# motorBoard.net
KiCad netlist of a schematic drawn in EAGLE
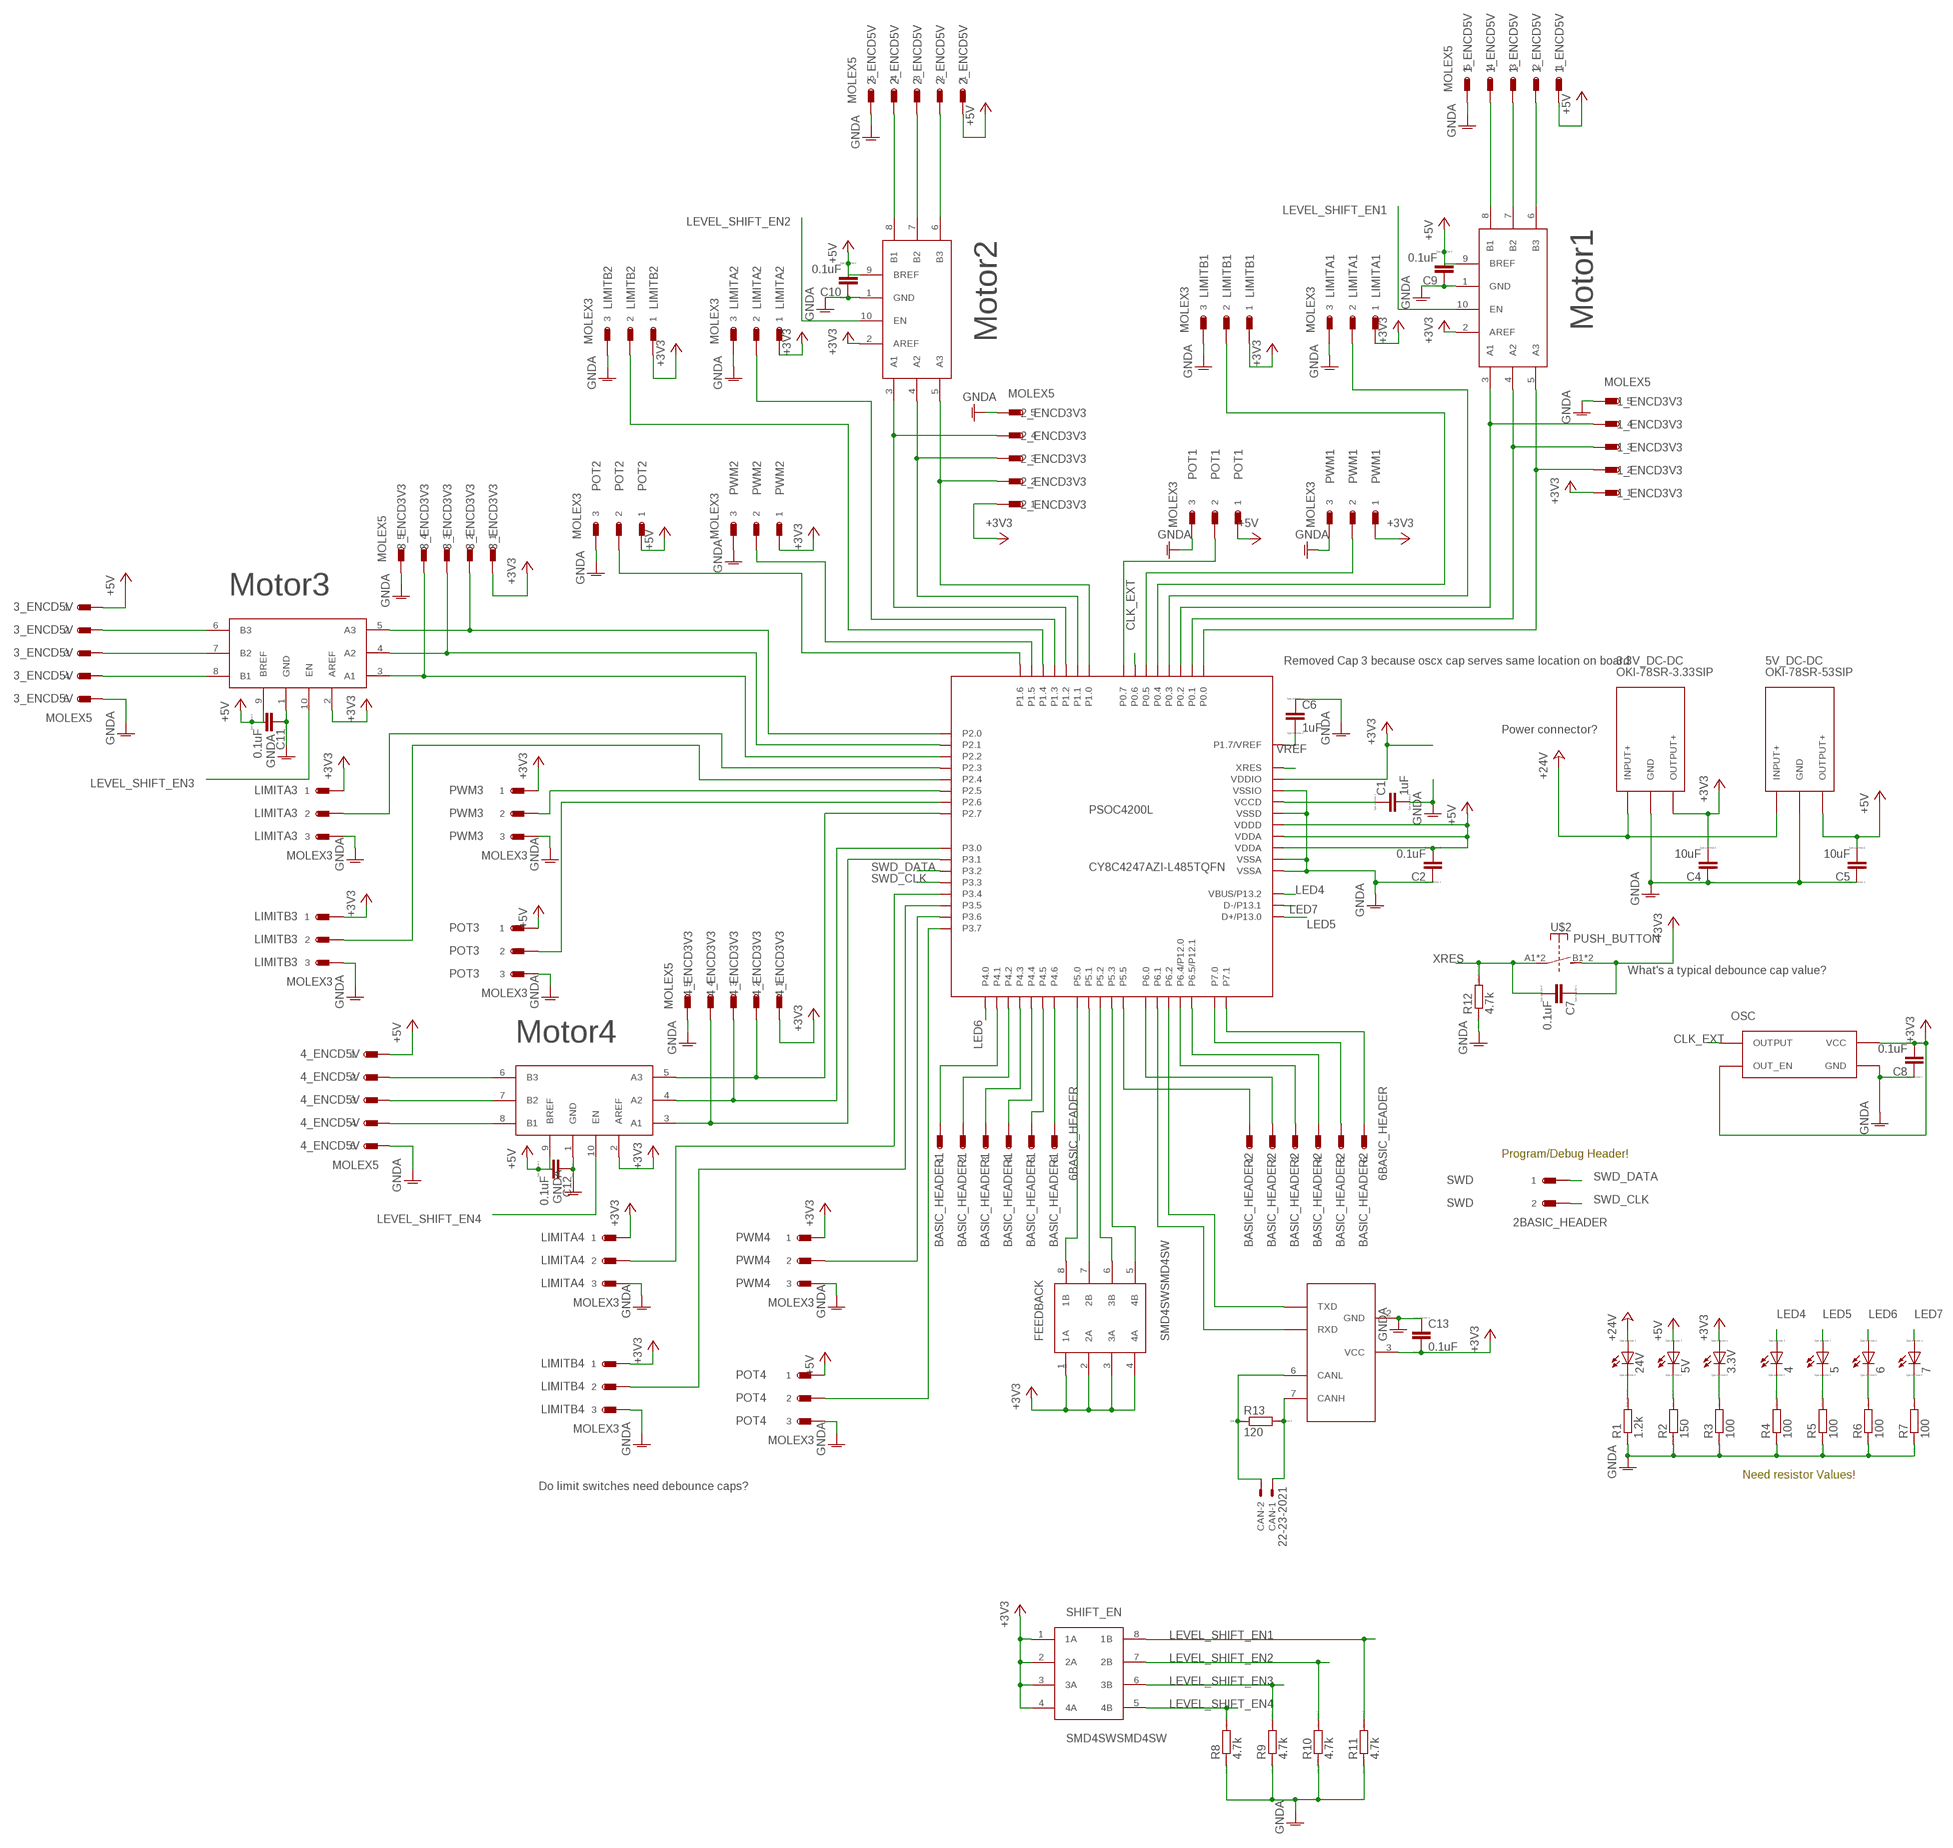
[diagram p0: schematic, sheet 1, part 1 of 2]
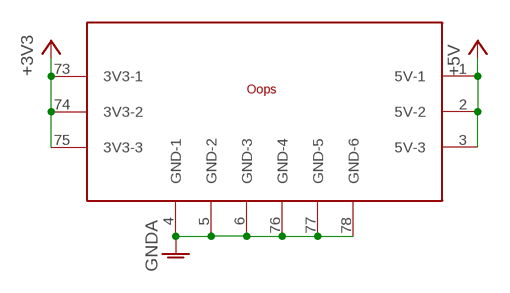
[diagram p1: schematic, sheet 1, part 2 of 2]

(export (version "E")
  (design (tool "Eeschema 10.0.6"))
  (components
    (comp (ref "1_ENCD3V3")
      (value "MOLEX5")
      (footprint "eagle-import:MOLEX22-23-2051")
      (libsource (lib "eagle-import") (part "MOLEX5"))
    )
    (comp (ref "1_ENCD5V")
      (value "MOLEX5")
      (footprint "eagle-import:MOLEX22-23-2051")
      (libsource (lib "eagle-import") (part "MOLEX5"))
    )
    (comp (ref "2_ENCD3V3")
      (value "MOLEX5")
      (footprint "eagle-import:MOLEX22-23-2051")
      (libsource (lib "eagle-import") (part "MOLEX5"))
    )
    (comp (ref "2_ENCD5V")
      (value "MOLEX5")
      (footprint "eagle-import:MOLEX22-23-2051")
      (libsource (lib "eagle-import") (part "MOLEX5"))
    )
    (comp (ref "3.3V")
      (value "LED_E")
      (footprint "eagle-import:LED_1206")
      (libsource (lib "eagle-import") (part "LED_E"))
    )
    (comp (ref "3.3V_DC-DC")
      (value "OKI-78SR-3.33SIP")
      (footprint "eagle-import:3SIP")
      (libsource (lib "eagle-import") (part "OKI-78SR-3.33SIP"))
    )
    (comp (ref "3_ENCD3V3")
      (value "MOLEX5")
      (footprint "eagle-import:MOLEX22-23-2051")
      (libsource (lib "eagle-import") (part "MOLEX5"))
    )
    (comp (ref "3_ENCD5V")
      (value "MOLEX5")
      (footprint "eagle-import:MOLEX22-23-2051")
      (libsource (lib "eagle-import") (part "MOLEX5"))
    )
    (comp (ref "4")
      (value "LED_E")
      (footprint "eagle-import:LED_1206")
      (libsource (lib "eagle-import") (part "LED_E"))
    )
    (comp (ref "4_ENCD3V3")
      (value "MOLEX5")
      (footprint "eagle-import:MOLEX22-23-2051")
      (libsource (lib "eagle-import") (part "MOLEX5"))
    )
    (comp (ref "4_ENCD5V")
      (value "MOLEX5")
      (footprint "eagle-import:MOLEX22-23-2051")
      (libsource (lib "eagle-import") (part "MOLEX5"))
    )
    (comp (ref "5")
      (value "LED_E")
      (footprint "eagle-import:LED_1206")
      (libsource (lib "eagle-import") (part "LED_E"))
    )
    (comp (ref "5V")
      (value "LED_E")
      (footprint "eagle-import:LED_1206")
      (libsource (lib "eagle-import") (part "LED_E"))
    )
    (comp (ref "5V_DC-DC")
      (value "OKI-78SR-53SIP")
      (footprint "eagle-import:3SIP")
      (libsource (lib "eagle-import") (part "OKI-78SR-53SIP"))
    )
    (comp (ref "6")
      (value "LED_E")
      (footprint "eagle-import:LED_1206")
      (libsource (lib "eagle-import") (part "LED_E"))
    )
    (comp (ref "7")
      (value "LED_E")
      (footprint "eagle-import:LED_1206")
      (libsource (lib "eagle-import") (part "LED_E"))
    )
    (comp (ref "24V")
      (value "LED_E")
      (footprint "eagle-import:LED_1206")
      (libsource (lib "eagle-import") (part "LED_E"))
    )
    (comp (ref "BASIC_HEADER1")
      (value "6BASIC_HEADER")
      (footprint "eagle-import:6SIP_HEADER")
      (libsource (lib "eagle-import") (part "6BASIC_HEADER"))
    )
    (comp (ref "BASIC_HEADER2")
      (value "6BASIC_HEADER")
      (footprint "eagle-import:6SIP_HEADER")
      (libsource (lib "eagle-import") (part "6BASIC_HEADER"))
    )
    (comp (ref "C1")
      (value "1uF")
      (footprint "eagle-import:C1206")
      (libsource (lib "eagle-import") (part "CC1206"))
    )
    (comp (ref "C2")
      (value "0.1uF")
      (footprint "eagle-import:C1206")
      (libsource (lib "eagle-import") (part "CC1206"))
    )
    (comp (ref "C4")
      (value "10uF")
      (footprint "eagle-import:C1206")
      (libsource (lib "eagle-import") (part "CC1206"))
    )
    (comp (ref "C5")
      (value "10uF")
      (footprint "eagle-import:C1206")
      (libsource (lib "eagle-import") (part "CC1206"))
    )
    (comp (ref "C6")
      (value "1uF")
      (footprint "eagle-import:C1206")
      (libsource (lib "eagle-import") (part "CC1206"))
    )
    (comp (ref "C7")
      (value "0.1uF")
      (footprint "eagle-import:C1206")
      (libsource (lib "eagle-import") (part "CC1206"))
    )
    (comp (ref "C8")
      (value "0.1uF")
      (footprint "eagle-import:C1206")
      (libsource (lib "eagle-import") (part "CC1206"))
    )
    (comp (ref "C9")
      (value "0.1uF")
      (footprint "eagle-import:C1206")
      (libsource (lib "eagle-import") (part "CC1206"))
    )
    (comp (ref "C10")
      (value "0.1uF")
      (footprint "eagle-import:C1206")
      (libsource (lib "eagle-import") (part "CC1206"))
    )
    (comp (ref "C11")
      (value "0.1uF")
      (footprint "eagle-import:C1206")
      (libsource (lib "eagle-import") (part "CC1206"))
    )
    (comp (ref "C12")
      (value "0.1uF")
      (footprint "eagle-import:C1206")
      (libsource (lib "eagle-import") (part "CC1206"))
    )
    (comp (ref "C13")
      (value "0.1uF")
      (footprint "eagle-import:C1206")
      (libsource (lib "eagle-import") (part "CC1206"))
    )
    (comp (ref "CAN")
      (value "22-23-2021")
      (footprint "eagle-import:22-23-2021")
      (fields (field (name "MF") "MOLEX"))
      (libsource (lib "eagle-import") (part "22-23-2021"))
    )
    (comp (ref "FEEDBACK")
      (value "SMD4SWSMD4SW")
      (footprint "eagle-import:GULL8")
      (libsource (lib "eagle-import") (part "SMD4SWSMD4SW"))
    )
    (comp (ref "LIMITA1")
      (value "MOLEX3")
      (footprint "eagle-import:MOLEX22-23-2031")
      (libsource (lib "eagle-import") (part "MOLEX3"))
    )
    (comp (ref "LIMITA2")
      (value "MOLEX3")
      (footprint "eagle-import:MOLEX22-23-2031")
      (libsource (lib "eagle-import") (part "MOLEX3"))
    )
    (comp (ref "LIMITA3")
      (value "MOLEX3")
      (footprint "eagle-import:MOLEX22-23-2031")
      (libsource (lib "eagle-import") (part "MOLEX3"))
    )
    (comp (ref "LIMITA4")
      (value "MOLEX3")
      (footprint "eagle-import:MOLEX22-23-2031")
      (libsource (lib "eagle-import") (part "MOLEX3"))
    )
    (comp (ref "LIMITB1")
      (value "MOLEX3")
      (footprint "eagle-import:MOLEX22-23-2031")
      (libsource (lib "eagle-import") (part "MOLEX3"))
    )
    (comp (ref "LIMITB2")
      (value "MOLEX3")
      (footprint "eagle-import:MOLEX22-23-2031")
      (libsource (lib "eagle-import") (part "MOLEX3"))
    )
    (comp (ref "LIMITB3")
      (value "MOLEX3")
      (footprint "eagle-import:MOLEX22-23-2031")
      (libsource (lib "eagle-import") (part "MOLEX3"))
    )
    (comp (ref "LIMITB4")
      (value "MOLEX3")
      (footprint "eagle-import:MOLEX22-23-2031")
      (libsource (lib "eagle-import") (part "MOLEX3"))
    )
    (comp (ref "OSC")
      (value "ESPSON_SG-646PCE_CRYSTAL_OSCILLATOREPSON_SG-646PCE_32MHZ")
      (footprint "eagle-import:4SOJ-5.08MM")
      (libsource (lib "eagle-import") (part "ESPSON_SG-646PCE_CRYSTAL_OSCILLATOREPSON_SG-646PCE_32MHZ"))
    )
    (comp (ref "POT1")
      (value "MOLEX3")
      (footprint "eagle-import:MOLEX22-23-2031")
      (libsource (lib "eagle-import") (part "MOLEX3"))
    )
    (comp (ref "POT2")
      (value "MOLEX3")
      (footprint "eagle-import:MOLEX22-23-2031")
      (libsource (lib "eagle-import") (part "MOLEX3"))
    )
    (comp (ref "POT3")
      (value "MOLEX3")
      (footprint "eagle-import:MOLEX22-23-2031")
      (libsource (lib "eagle-import") (part "MOLEX3"))
    )
    (comp (ref "POT4")
      (value "MOLEX3")
      (footprint "eagle-import:MOLEX22-23-2031")
      (libsource (lib "eagle-import") (part "MOLEX3"))
    )
    (comp (ref "PSOC4200L")
      (value "CY8C4247AZI-L485TQFN")
      (footprint "eagle-import:TQPF64-10MM")
      (libsource (lib "eagle-import") (part "CY8C4247AZI-L485TQFN"))
    )
    (comp (ref "PWM1")
      (value "MOLEX3")
      (footprint "eagle-import:MOLEX22-23-2031")
      (libsource (lib "eagle-import") (part "MOLEX3"))
    )
    (comp (ref "PWM2")
      (value "MOLEX3")
      (footprint "eagle-import:MOLEX22-23-2031")
      (libsource (lib "eagle-import") (part "MOLEX3"))
    )
    (comp (ref "PWM3")
      (value "MOLEX3")
      (footprint "eagle-import:MOLEX22-23-2031")
      (libsource (lib "eagle-import") (part "MOLEX3"))
    )
    (comp (ref "PWM4")
      (value "MOLEX3")
      (footprint "eagle-import:MOLEX22-23-2031")
      (libsource (lib "eagle-import") (part "MOLEX3"))
    )
    (comp (ref "R1")
      (value "1.2k")
      (footprint "eagle-import:R1206")
      (libsource (lib "eagle-import") (part "RR1206"))
    )
    (comp (ref "R2")
      (value "150")
      (footprint "eagle-import:R1206")
      (libsource (lib "eagle-import") (part "RR1206"))
    )
    (comp (ref "R3")
      (value "100")
      (footprint "eagle-import:R1206")
      (libsource (lib "eagle-import") (part "RR1206"))
    )
    (comp (ref "R4")
      (value "100")
      (footprint "eagle-import:R1206")
      (libsource (lib "eagle-import") (part "RR1206"))
    )
    (comp (ref "R5")
      (value "100")
      (footprint "eagle-import:R1206")
      (libsource (lib "eagle-import") (part "RR1206"))
    )
    (comp (ref "R6")
      (value "100")
      (footprint "eagle-import:R1206")
      (libsource (lib "eagle-import") (part "RR1206"))
    )
    (comp (ref "R7")
      (value "100")
      (footprint "eagle-import:R1206")
      (libsource (lib "eagle-import") (part "RR1206"))
    )
    (comp (ref "R8")
      (value "4.7k")
      (footprint "eagle-import:R1206")
      (libsource (lib "eagle-import") (part "RR1206"))
    )
    (comp (ref "R9")
      (value "4.7k")
      (footprint "eagle-import:R1206")
      (libsource (lib "eagle-import") (part "RR1206"))
    )
    (comp (ref "R10")
      (value "4.7k")
      (footprint "eagle-import:R1206")
      (libsource (lib "eagle-import") (part "RR1206"))
    )
    (comp (ref "R11")
      (value "4.7k")
      (footprint "eagle-import:R1206")
      (libsource (lib "eagle-import") (part "RR1206"))
    )
    (comp (ref "R12")
      (value "4.7k")
      (footprint "eagle-import:R1206")
      (libsource (lib "eagle-import") (part "RR1206"))
    )
    (comp (ref "R13")
      (value "120")
      (footprint "eagle-import:R1206")
      (libsource (lib "eagle-import") (part "RR1206"))
    )
    (comp (ref "SHIFT1")
      (value "LEVEL-SHIFTER_NVT2003DPNVT_2003DP_LEVEL_SHIFTER")
      (footprint "eagle-import:TSSOP10")
      (libsource (lib "eagle-import") (part "LEVEL-SHIFTER_NVT2003DPNVT_2003DP_LEVEL_SHIFTER"))
    )
    (comp (ref "SHIFT2")
      (value "LEVEL-SHIFTER_NVT2003DPNVT_2003DP_LEVEL_SHIFTER")
      (footprint "eagle-import:TSSOP10")
      (libsource (lib "eagle-import") (part "LEVEL-SHIFTER_NVT2003DPNVT_2003DP_LEVEL_SHIFTER"))
    )
    (comp (ref "SHIFT3")
      (value "LEVEL-SHIFTER_NVT2003DPNVT_2003DP_LEVEL_SHIFTER")
      (footprint "eagle-import:TSSOP10")
      (libsource (lib "eagle-import") (part "LEVEL-SHIFTER_NVT2003DPNVT_2003DP_LEVEL_SHIFTER"))
    )
    (comp (ref "SHIFT4")
      (value "LEVEL-SHIFTER_NVT2003DPNVT_2003DP_LEVEL_SHIFTER")
      (footprint "eagle-import:TSSOP10")
      (libsource (lib "eagle-import") (part "LEVEL-SHIFTER_NVT2003DPNVT_2003DP_LEVEL_SHIFTER"))
    )
    (comp (ref "SHIFT_EN")
      (value "SMD4SWSMD4SW")
      (footprint "eagle-import:GULL8")
      (libsource (lib "eagle-import") (part "SMD4SWSMD4SW"))
    )
    (comp (ref "SWD")
      (value "2BASIC_HEADER")
      (footprint "eagle-import:2SIP_HEADER")
      (libsource (lib "eagle-import") (part "2BASIC_HEADER"))
    )
    (comp (ref "TCAN")
      (value "TCAN332TCAN332")
      (footprint "eagle-import:8SOIC3.9")
      (libsource (lib "eagle-import") (part "TCAN332TCAN332"))
    )
    (comp (ref "U$1")
      (value "OOPS_SPACE")
      (footprint "eagle-import:OOPS_SPACE")
      (libsource (lib "eagle-import") (part "OOPS_SPACE"))
    )
    (comp (ref "U$2")
      (value "PUSH_BUTTON")
      (footprint "eagle-import:PUSH_BUTTON")
      (libsource (lib "eagle-import") (part "PUSH_BUTTON"))
    )
  )
  (nets
    (net (code "1") (name "+3V3") (class "Default")
      (node (ref "1_ENCD3V3") (pin "1") (pinfunction "1_1") (pintype "bidirectional"))
      (node (ref "2_ENCD3V3") (pin "1") (pinfunction "1_1") (pintype "bidirectional"))
      (node (ref "3.3V") (pin "A") (pinfunction "A_A") (pintype "passive"))
      (node (ref "3.3V_DC-DC") (pin "3") (pinfunction "OUTPUT+_3") (pintype "power_in"))
      (node (ref "3_ENCD3V3") (pin "1") (pinfunction "1_1") (pintype "bidirectional"))
      (node (ref "4_ENCD3V3") (pin "1") (pinfunction "1_1") (pintype "bidirectional"))
      (node (ref "C13") (pin "2") (pinfunction "2_2") (pintype "passive"))
      (node (ref "C4") (pin "2") (pinfunction "2_2") (pintype "passive"))
      (node (ref "C7") (pin "1") (pinfunction "1_1") (pintype "passive"))
      (node (ref "C8") (pin "2") (pinfunction "2_2") (pintype "passive"))
      (node (ref "FEEDBACK") (pin "1") (pinfunction "1A_1") (pintype "bidirectional"))
      (node (ref "FEEDBACK") (pin "2") (pinfunction "2A_2") (pintype "bidirectional"))
      (node (ref "FEEDBACK") (pin "3") (pinfunction "3A_3") (pintype "bidirectional"))
      (node (ref "FEEDBACK") (pin "4") (pinfunction "4A_4") (pintype "bidirectional"))
      (node (ref "LIMITA1") (pin "1") (pinfunction "1_1") (pintype "bidirectional"))
      (node (ref "LIMITA2") (pin "1") (pinfunction "1_1") (pintype "bidirectional"))
      (node (ref "LIMITA3") (pin "1") (pinfunction "1_1") (pintype "bidirectional"))
      (node (ref "LIMITA4") (pin "1") (pinfunction "1_1") (pintype "bidirectional"))
      (node (ref "LIMITB1") (pin "1") (pinfunction "1_1") (pintype "bidirectional"))
      (node (ref "LIMITB2") (pin "1") (pinfunction "1_1") (pintype "bidirectional"))
      (node (ref "LIMITB3") (pin "1") (pinfunction "1_1") (pintype "bidirectional"))
      (node (ref "LIMITB4") (pin "1") (pinfunction "1_1") (pintype "bidirectional"))
      (node (ref "OSC") (pin "1") (pinfunction "OUT_EN_1") (pintype "input"))
      (node (ref "OSC") (pin "4") (pinfunction "VCC_4") (pintype "power_in"))
      (node (ref "PSOC4200L") (pin "26") (pinfunction "VDDIO_26") (pintype "power_in"))
      (node (ref "PWM1") (pin "1") (pinfunction "1_1") (pintype "bidirectional"))
      (node (ref "PWM2") (pin "1") (pinfunction "1_1") (pintype "bidirectional"))
      (node (ref "PWM3") (pin "1") (pinfunction "1_1") (pintype "bidirectional"))
      (node (ref "PWM4") (pin "1") (pinfunction "1_1") (pintype "bidirectional"))
      (node (ref "SHIFT1") (pin "2") (pinfunction "AREF_2") (pintype "bidirectional"))
      (node (ref "SHIFT2") (pin "2") (pinfunction "AREF_2") (pintype "bidirectional"))
      (node (ref "SHIFT3") (pin "2") (pinfunction "AREF_2") (pintype "bidirectional"))
      (node (ref "SHIFT4") (pin "2") (pinfunction "AREF_2") (pintype "bidirectional"))
      (node (ref "SHIFT_EN") (pin "1") (pinfunction "1A_1") (pintype "bidirectional"))
      (node (ref "SHIFT_EN") (pin "2") (pinfunction "2A_2") (pintype "bidirectional"))
      (node (ref "SHIFT_EN") (pin "3") (pinfunction "3A_3") (pintype "bidirectional"))
      (node (ref "SHIFT_EN") (pin "4") (pinfunction "4A_4") (pintype "bidirectional"))
      (node (ref "TCAN") (pin "3") (pinfunction "VCC_3") (pintype "power_in"))
      (node (ref "U$1") (pin "73") (pinfunction "3V3-1_73") (pintype "bidirectional"))
      (node (ref "U$1") (pin "74") (pinfunction "3V3-2_74") (pintype "bidirectional"))
      (node (ref "U$1") (pin "75") (pinfunction "3V3-3_75") (pintype "bidirectional"))
      (node (ref "U$2") (pin "B1") (pinfunction "S_B1") (pintype "passive"))
      (node (ref "U$2") (pin "B2") (pinfunction "S_B2") (pintype "passive"))
    )
    (net (code "2") (name "+5V") (class "Default")
      (node (ref "1_ENCD5V") (pin "1") (pinfunction "1_1") (pintype "bidirectional"))
      (node (ref "2_ENCD5V") (pin "1") (pinfunction "1_1") (pintype "bidirectional"))
      (node (ref "3_ENCD5V") (pin "1") (pinfunction "1_1") (pintype "bidirectional"))
      (node (ref "4_ENCD5V") (pin "1") (pinfunction "1_1") (pintype "bidirectional"))
      (node (ref "5V") (pin "A") (pinfunction "A_A") (pintype "passive"))
      (node (ref "5V_DC-DC") (pin "3") (pinfunction "OUTPUT+_3") (pintype "power_in"))
      (node (ref "C10") (pin "2") (pinfunction "2_2") (pintype "passive"))
      (node (ref "C11") (pin "2") (pinfunction "2_2") (pintype "passive"))
      (node (ref "C12") (pin "2") (pinfunction "2_2") (pintype "passive"))
      (node (ref "C2") (pin "2") (pinfunction "2_2") (pintype "passive"))
      (node (ref "C5") (pin "2") (pinfunction "2_2") (pintype "passive"))
      (node (ref "C9") (pin "2") (pinfunction "2_2") (pintype "passive"))
      (node (ref "POT1") (pin "1") (pinfunction "1_1") (pintype "bidirectional"))
      (node (ref "POT2") (pin "1") (pinfunction "1_1") (pintype "bidirectional"))
      (node (ref "POT3") (pin "1") (pinfunction "1_1") (pintype "bidirectional"))
      (node (ref "POT4") (pin "1") (pinfunction "1_1") (pintype "bidirectional"))
      (node (ref "PSOC4200L") (pin "11") (pinfunction "VDDA_11") (pintype "power_in"))
      (node (ref "PSOC4200L") (pin "50") (pinfunction "VDDD_50") (pintype "power_in"))
      (node (ref "PSOC4200L") (pin "56") (pinfunction "VDDA_56") (pintype "power_in"))
      (node (ref "SHIFT1") (pin "9") (pinfunction "BREF_9") (pintype "bidirectional"))
      (node (ref "SHIFT2") (pin "9") (pinfunction "BREF_9") (pintype "bidirectional"))
      (node (ref "SHIFT3") (pin "9") (pinfunction "BREF_9") (pintype "bidirectional"))
      (node (ref "SHIFT4") (pin "9") (pinfunction "BREF_9") (pintype "bidirectional"))
      (node (ref "U$1") (pin "1") (pinfunction "5V-1_1") (pintype "bidirectional"))
      (node (ref "U$1") (pin "2") (pinfunction "5V-2_2") (pintype "bidirectional"))
      (node (ref "U$1") (pin "3") (pinfunction "5V-3_3") (pintype "bidirectional"))
    )
    (net (code "3") (name "+24V") (class "Default")
      (node (ref "24V") (pin "A") (pinfunction "A_A") (pintype "passive"))
      (node (ref "3.3V_DC-DC") (pin "1") (pinfunction "INPUT+_1") (pintype "power_in"))
      (node (ref "5V_DC-DC") (pin "1") (pinfunction "INPUT+_1") (pintype "power_in"))
    )
    (net (code "4") (name "/CLK_EXT") (class "Default")
      (node (ref "OSC") (pin "3") (pinfunction "OUTPUT_3") (pintype "output"))
      (node (ref "PSOC4200L") (pin "45") (pinfunction "P0.6_45") (pintype "bidirectional"))
    )
    (net (code "5") (name "/LED4") (class "Default")
      (node (ref "4") (pin "A") (pinfunction "A_A") (pintype "passive"))
      (node (ref "PSOC4200L") (pin "36") (pinfunction "VBUS/P13.2_36") (pintype "bidirectional"))
    )
    (net (code "6") (name "/LED5") (class "Default")
      (node (ref "5") (pin "A") (pinfunction "A_A") (pintype "passive"))
      (node (ref "PSOC4200L") (pin "34") (pinfunction "D+/P13.0_34") (pintype "bidirectional"))
    )
    (net (code "7") (name "/LED6") (class "Default")
      (node (ref "6") (pin "A") (pinfunction "A_A") (pintype "passive"))
      (node (ref "PSOC4200L") (pin "27") (pinfunction "P4.0_27") (pintype "bidirectional"))
    )
    (net (code "8") (name "/LED7") (class "Default")
      (node (ref "7") (pin "A") (pinfunction "A_A") (pintype "passive"))
      (node (ref "PSOC4200L") (pin "35") (pinfunction "D-/P13.1_35") (pintype "bidirectional"))
    )
    (net (code "9") (name "/LEVEL_SHIFT_EN1") (class "Default")
      (node (ref "R11") (pin "2") (pinfunction "2_2") (pintype "passive"))
      (node (ref "SHIFT1") (pin "10") (pinfunction "EN_10") (pintype "bidirectional"))
      (node (ref "SHIFT_EN") (pin "8") (pinfunction "1B_8") (pintype "bidirectional"))
    )
    (net (code "10") (name "/LEVEL_SHIFT_EN2") (class "Default")
      (node (ref "R10") (pin "2") (pinfunction "2_2") (pintype "passive"))
      (node (ref "SHIFT2") (pin "10") (pinfunction "EN_10") (pintype "bidirectional"))
      (node (ref "SHIFT_EN") (pin "7") (pinfunction "2B_7") (pintype "bidirectional"))
    )
    (net (code "11") (name "/LEVEL_SHIFT_EN3") (class "Default")
      (node (ref "R9") (pin "2") (pinfunction "2_2") (pintype "passive"))
      (node (ref "SHIFT3") (pin "10") (pinfunction "EN_10") (pintype "bidirectional"))
      (node (ref "SHIFT_EN") (pin "6") (pinfunction "3B_6") (pintype "bidirectional"))
    )
    (net (code "12") (name "/LEVEL_SHIFT_EN4") (class "Default")
      (node (ref "R8") (pin "2") (pinfunction "2_2") (pintype "passive"))
      (node (ref "SHIFT4") (pin "10") (pinfunction "EN_10") (pintype "bidirectional"))
      (node (ref "SHIFT_EN") (pin "5") (pinfunction "4B_5") (pintype "bidirectional"))
    )
    (net (code "13") (name "/SWD_CLK") (class "Default")
      (node (ref "PSOC4200L") (pin "21") (pinfunction "P3.3_21") (pintype "bidirectional"))
      (node (ref "SWD") (pin "2") (pinfunction "2_2") (pintype "bidirectional"))
    )
    (net (code "14") (name "/SWD_DATA") (class "Default")
      (node (ref "PSOC4200L") (pin "20") (pinfunction "P3.2_20") (pintype "bidirectional"))
      (node (ref "SWD") (pin "1") (pinfunction "1_1") (pintype "bidirectional"))
    )
    (net (code "15") (name "/VREF") (class "Default")
      (node (ref "C6") (pin "2") (pinfunction "2_2") (pintype "passive"))
      (node (ref "PSOC4200L") (pin "1") (pinfunction "P1.7/VREF_1") (pintype "bidirectional"))
    )
    (net (code "16") (name "/XRES") (class "Default")
      (node (ref "C7") (pin "2") (pinfunction "2_2") (pintype "passive"))
      (node (ref "PSOC4200L") (pin "47") (pinfunction "XRES_47") (pintype "input"))
      (node (ref "R12") (pin "2") (pinfunction "2_2") (pintype "passive"))
      (node (ref "U$2") (pin "A1") (pinfunction "P_A1") (pintype "passive"))
      (node (ref "U$2") (pin "A2") (pinfunction "P_A2") (pintype "passive"))
    )
    (net (code "17") (name "GNDA") (class "Default")
      (node (ref "1_ENCD3V3") (pin "5") (pinfunction "5_5") (pintype "bidirectional"))
      (node (ref "1_ENCD5V") (pin "5") (pinfunction "5_5") (pintype "bidirectional"))
      (node (ref "2_ENCD3V3") (pin "5") (pinfunction "5_5") (pintype "bidirectional"))
      (node (ref "2_ENCD5V") (pin "5") (pinfunction "5_5") (pintype "bidirectional"))
      (node (ref "3.3V_DC-DC") (pin "2") (pinfunction "GND_2") (pintype "power_in"))
      (node (ref "3_ENCD3V3") (pin "5") (pinfunction "5_5") (pintype "bidirectional"))
      (node (ref "3_ENCD5V") (pin "5") (pinfunction "5_5") (pintype "bidirectional"))
      (node (ref "4_ENCD3V3") (pin "5") (pinfunction "5_5") (pintype "bidirectional"))
      (node (ref "4_ENCD5V") (pin "5") (pinfunction "5_5") (pintype "bidirectional"))
      (node (ref "5V_DC-DC") (pin "2") (pinfunction "GND_2") (pintype "power_in"))
      (node (ref "C1") (pin "2") (pinfunction "2_2") (pintype "passive"))
      (node (ref "C10") (pin "1") (pinfunction "1_1") (pintype "passive"))
      (node (ref "C11") (pin "1") (pinfunction "1_1") (pintype "passive"))
      (node (ref "C12") (pin "1") (pinfunction "1_1") (pintype "passive"))
      (node (ref "C13") (pin "1") (pinfunction "1_1") (pintype "passive"))
      (node (ref "C2") (pin "1") (pinfunction "1_1") (pintype "passive"))
      (node (ref "C4") (pin "1") (pinfunction "1_1") (pintype "passive"))
      (node (ref "C5") (pin "1") (pinfunction "1_1") (pintype "passive"))
      (node (ref "C6") (pin "1") (pinfunction "1_1") (pintype "passive"))
      (node (ref "C8") (pin "1") (pinfunction "1_1") (pintype "passive"))
      (node (ref "C9") (pin "1") (pinfunction "1_1") (pintype "passive"))
      (node (ref "LIMITA1") (pin "3") (pinfunction "3_3") (pintype "bidirectional"))
      (node (ref "LIMITA2") (pin "3") (pinfunction "3_3") (pintype "bidirectional"))
      (node (ref "LIMITA3") (pin "3") (pinfunction "3_3") (pintype "bidirectional"))
      (node (ref "LIMITA4") (pin "3") (pinfunction "3_3") (pintype "bidirectional"))
      (node (ref "LIMITB1") (pin "3") (pinfunction "3_3") (pintype "bidirectional"))
      (node (ref "LIMITB2") (pin "3") (pinfunction "3_3") (pintype "bidirectional"))
      (node (ref "LIMITB3") (pin "3") (pinfunction "3_3") (pintype "bidirectional"))
      (node (ref "LIMITB4") (pin "3") (pinfunction "3_3") (pintype "bidirectional"))
      (node (ref "OSC") (pin "2") (pinfunction "GND_2") (pintype "power_in"))
      (node (ref "POT1") (pin "3") (pinfunction "3_3") (pintype "bidirectional"))
      (node (ref "POT2") (pin "3") (pinfunction "3_3") (pintype "bidirectional"))
      (node (ref "POT3") (pin "3") (pinfunction "3_3") (pintype "bidirectional"))
      (node (ref "POT4") (pin "3") (pinfunction "3_3") (pintype "bidirectional"))
      (node (ref "PSOC4200L") (pin "10") (pinfunction "VSSA_10") (pintype "power_in"))
      (node (ref "PSOC4200L") (pin "17") (pinfunction "VSSIO_17") (pintype "power_in"))
      (node (ref "PSOC4200L") (pin "49") (pinfunction "VSSD_49") (pintype "power_in"))
      (node (ref "PSOC4200L") (pin "57") (pinfunction "VSSA_57") (pintype "bidirectional"))
      (node (ref "PWM1") (pin "3") (pinfunction "3_3") (pintype "bidirectional"))
      (node (ref "PWM2") (pin "3") (pinfunction "3_3") (pintype "bidirectional"))
      (node (ref "PWM3") (pin "3") (pinfunction "3_3") (pintype "bidirectional"))
      (node (ref "PWM4") (pin "3") (pinfunction "3_3") (pintype "bidirectional"))
      (node (ref "R1") (pin "1") (pinfunction "1_1") (pintype "passive"))
      (node (ref "R10") (pin "1") (pinfunction "1_1") (pintype "passive"))
      (node (ref "R11") (pin "1") (pinfunction "1_1") (pintype "passive"))
      (node (ref "R12") (pin "1") (pinfunction "1_1") (pintype "passive"))
      (node (ref "R2") (pin "1") (pinfunction "1_1") (pintype "passive"))
      (node (ref "R3") (pin "1") (pinfunction "1_1") (pintype "passive"))
      (node (ref "R4") (pin "1") (pinfunction "1_1") (pintype "passive"))
      (node (ref "R5") (pin "1") (pinfunction "1_1") (pintype "passive"))
      (node (ref "R6") (pin "1") (pinfunction "1_1") (pintype "passive"))
      (node (ref "R7") (pin "1") (pinfunction "1_1") (pintype "passive"))
      (node (ref "R8") (pin "1") (pinfunction "1_1") (pintype "passive"))
      (node (ref "R9") (pin "1") (pinfunction "1_1") (pintype "passive"))
      (node (ref "SHIFT1") (pin "1") (pinfunction "GND_1") (pintype "bidirectional"))
      (node (ref "SHIFT2") (pin "1") (pinfunction "GND_1") (pintype "bidirectional"))
      (node (ref "SHIFT3") (pin "1") (pinfunction "GND_1") (pintype "bidirectional"))
      (node (ref "SHIFT4") (pin "1") (pinfunction "GND_1") (pintype "bidirectional"))
      (node (ref "TCAN") (pin "2") (pinfunction "GND_2") (pintype "power_in"))
      (node (ref "U$1") (pin "4") (pinfunction "GND-1_4") (pintype "bidirectional"))
      (node (ref "U$1") (pin "5") (pinfunction "GND-2_5") (pintype "bidirectional"))
      (node (ref "U$1") (pin "6") (pinfunction "GND-3_6") (pintype "bidirectional"))
      (node (ref "U$1") (pin "76") (pinfunction "GND-4_76") (pintype "bidirectional"))
      (node (ref "U$1") (pin "77") (pinfunction "GND-5_77") (pintype "bidirectional"))
      (node (ref "U$1") (pin "78") (pinfunction "GND-6_78") (pintype "bidirectional"))
    )
    (net (code "18") (name "Net-(3.3V-PadC)") (class "Default")
      (node (ref "3.3V") (pin "C") (pinfunction "C_C") (pintype "passive"))
      (node (ref "R3") (pin "2") (pinfunction "2_2") (pintype "passive"))
    )
    (net (code "19") (name "Net-(4-PadC)") (class "Default")
      (node (ref "4") (pin "C") (pinfunction "C_C") (pintype "passive"))
      (node (ref "R4") (pin "2") (pinfunction "2_2") (pintype "passive"))
    )
    (net (code "20") (name "Net-(5-PadC)") (class "Default")
      (node (ref "5") (pin "C") (pinfunction "C_C") (pintype "passive"))
      (node (ref "R5") (pin "2") (pinfunction "2_2") (pintype "passive"))
    )
    (net (code "21") (name "Net-(5V-PadC)") (class "Default")
      (node (ref "5V") (pin "C") (pinfunction "C_C") (pintype "passive"))
      (node (ref "R2") (pin "2") (pinfunction "2_2") (pintype "passive"))
    )
    (net (code "22") (name "Net-(6-PadC)") (class "Default")
      (node (ref "6") (pin "C") (pinfunction "C_C") (pintype "passive"))
      (node (ref "R6") (pin "2") (pinfunction "2_2") (pintype "passive"))
    )
    (net (code "23") (name "Net-(7-PadC)") (class "Default")
      (node (ref "7") (pin "C") (pinfunction "C_C") (pintype "passive"))
      (node (ref "R7") (pin "2") (pinfunction "2_2") (pintype "passive"))
    )
    (net (code "24") (name "Net-(24V-PadC)") (class "Default")
      (node (ref "24V") (pin "C") (pinfunction "C_C") (pintype "passive"))
      (node (ref "R1") (pin "2") (pinfunction "2_2") (pintype "passive"))
    )
    (net (code "25") (name "Net-(CANA-S)") (class "Default")
      (node (ref "CAN") (pin "1") (pinfunction "S_1") (pintype "passive"))
      (node (ref "R13") (pin "2") (pinfunction "2_2") (pintype "passive"))
      (node (ref "TCAN") (pin "7") (pinfunction "CANH_7") (pintype "bidirectional"))
    )
    (net (code "26") (name "Net-(CANB-S)") (class "Default")
      (node (ref "CAN") (pin "2") (pinfunction "S_2") (pintype "passive"))
      (node (ref "R13") (pin "1") (pinfunction "1_1") (pintype "passive"))
      (node (ref "TCAN") (pin "6") (pinfunction "CANL_6") (pintype "bidirectional"))
    )
    (net (code "27") (name "Net-(FEEDBACK-1B)") (class "Default")
      (node (ref "FEEDBACK") (pin "8") (pinfunction "1B_8") (pintype "bidirectional"))
      (node (ref "PSOC4200L") (pin "51") (pinfunction "P5.0_51") (pintype "bidirectional"))
    )
    (net (code "28") (name "Net-(FEEDBACK-2B)") (class "Default")
      (node (ref "FEEDBACK") (pin "7") (pinfunction "2B_7") (pintype "bidirectional"))
      (node (ref "PSOC4200L") (pin "52") (pinfunction "P5.1_52") (pintype "bidirectional"))
    )
    (net (code "29") (name "Net-(FEEDBACK-3B)") (class "Default")
      (node (ref "FEEDBACK") (pin "6") (pinfunction "3B_6") (pintype "bidirectional"))
      (node (ref "PSOC4200L") (pin "53") (pinfunction "P5.2_53") (pintype "bidirectional"))
    )
    (net (code "30") (name "Net-(FEEDBACK-4B)") (class "Default")
      (node (ref "FEEDBACK") (pin "5") (pinfunction "4B_5") (pintype "bidirectional"))
      (node (ref "PSOC4200L") (pin "54") (pinfunction "P5.3_54") (pintype "bidirectional"))
    )
    (net (code "31") (name "Net-(PSOC4200L-P0.0)") (class "Default")
      (node (ref "1_ENCD3V3") (pin "2") (pinfunction "2_2") (pintype "bidirectional"))
      (node (ref "PSOC4200L") (pin "39") (pinfunction "P0.0_39") (pintype "bidirectional"))
      (node (ref "SHIFT1") (pin "5") (pinfunction "A3_5") (pintype "bidirectional"))
    )
    (net (code "32") (name "Net-(PSOC4200L-P0.1)") (class "Default")
      (node (ref "1_ENCD3V3") (pin "3") (pinfunction "3_3") (pintype "bidirectional"))
      (node (ref "PSOC4200L") (pin "40") (pinfunction "P0.1_40") (pintype "bidirectional"))
      (node (ref "SHIFT1") (pin "4") (pinfunction "A2_4") (pintype "bidirectional"))
    )
    (net (code "33") (name "Net-(PSOC4200L-P0.2)") (class "Default")
      (node (ref "1_ENCD3V3") (pin "4") (pinfunction "4_4") (pintype "bidirectional"))
      (node (ref "PSOC4200L") (pin "41") (pinfunction "P0.2_41") (pintype "bidirectional"))
      (node (ref "SHIFT1") (pin "3") (pinfunction "A1_3") (pintype "bidirectional"))
    )
    (net (code "34") (name "Net-(PSOC4200L-P0.3)") (class "Default")
      (node (ref "LIMITA1") (pin "2") (pinfunction "2_2") (pintype "bidirectional"))
      (node (ref "PSOC4200L") (pin "42") (pinfunction "P0.3_42") (pintype "bidirectional"))
    )
    (net (code "35") (name "Net-(PSOC4200L-P0.4)") (class "Default")
      (node (ref "LIMITB1") (pin "2") (pinfunction "2_2") (pintype "bidirectional"))
      (node (ref "PSOC4200L") (pin "43") (pinfunction "P0.4_43") (pintype "bidirectional"))
    )
    (net (code "36") (name "Net-(PSOC4200L-P0.5)") (class "Default")
      (node (ref "PSOC4200L") (pin "44") (pinfunction "P0.5_44") (pintype "bidirectional"))
      (node (ref "PWM1") (pin "2") (pinfunction "2_2") (pintype "bidirectional"))
    )
    (net (code "37") (name "Net-(PSOC4200L-P0.7)") (class "Default")
      (node (ref "POT1") (pin "2") (pinfunction "2_2") (pintype "bidirectional"))
      (node (ref "PSOC4200L") (pin "46") (pinfunction "P0.7_46") (pintype "bidirectional"))
    )
    (net (code "38") (name "Net-(PSOC4200L-P1.0)") (class "Default")
      (node (ref "2_ENCD3V3") (pin "2") (pinfunction "2_2") (pintype "bidirectional"))
      (node (ref "PSOC4200L") (pin "58") (pinfunction "P1.0_58") (pintype "bidirectional"))
      (node (ref "SHIFT2") (pin "5") (pinfunction "A3_5") (pintype "bidirectional"))
    )
    (net (code "39") (name "Net-(PSOC4200L-P1.1)") (class "Default")
      (node (ref "2_ENCD3V3") (pin "3") (pinfunction "3_3") (pintype "bidirectional"))
      (node (ref "PSOC4200L") (pin "59") (pinfunction "P1.1_59") (pintype "bidirectional"))
      (node (ref "SHIFT2") (pin "4") (pinfunction "A2_4") (pintype "bidirectional"))
    )
    (net (code "40") (name "Net-(PSOC4200L-P1.2)") (class "Default")
      (node (ref "2_ENCD3V3") (pin "4") (pinfunction "4_4") (pintype "bidirectional"))
      (node (ref "PSOC4200L") (pin "60") (pinfunction "P1.2_60") (pintype "bidirectional"))
      (node (ref "SHIFT2") (pin "3") (pinfunction "A1_3") (pintype "bidirectional"))
    )
    (net (code "41") (name "Net-(PSOC4200L-P1.3)") (class "Default")
      (node (ref "LIMITA2") (pin "2") (pinfunction "2_2") (pintype "bidirectional"))
      (node (ref "PSOC4200L") (pin "61") (pinfunction "P1.3_61") (pintype "bidirectional"))
    )
    (net (code "42") (name "Net-(PSOC4200L-P1.4)") (class "Default")
      (node (ref "LIMITB2") (pin "2") (pinfunction "2_2") (pintype "bidirectional"))
      (node (ref "PSOC4200L") (pin "62") (pinfunction "P1.4_62") (pintype "bidirectional"))
    )
    (net (code "43") (name "Net-(PSOC4200L-P1.5)") (class "Default")
      (node (ref "PSOC4200L") (pin "63") (pinfunction "P1.5_63") (pintype "bidirectional"))
      (node (ref "PWM2") (pin "2") (pinfunction "2_2") (pintype "bidirectional"))
    )
    (net (code "44") (name "Net-(PSOC4200L-P1.6)") (class "Default")
      (node (ref "POT2") (pin "2") (pinfunction "2_2") (pintype "bidirectional"))
      (node (ref "PSOC4200L") (pin "64") (pinfunction "P1.6_64") (pintype "bidirectional"))
    )
    (net (code "45") (name "Net-(PSOC4200L-P2.0)") (class "Default")
      (node (ref "3_ENCD3V3") (pin "2") (pinfunction "2_2") (pintype "bidirectional"))
      (node (ref "PSOC4200L") (pin "2") (pinfunction "P2.0_2") (pintype "bidirectional"))
      (node (ref "SHIFT3") (pin "5") (pinfunction "A3_5") (pintype "bidirectional"))
    )
    (net (code "46") (name "Net-(PSOC4200L-P2.1)") (class "Default")
      (node (ref "3_ENCD3V3") (pin "3") (pinfunction "3_3") (pintype "bidirectional"))
      (node (ref "PSOC4200L") (pin "3") (pinfunction "P2.1_3") (pintype "bidirectional"))
      (node (ref "SHIFT3") (pin "4") (pinfunction "A2_4") (pintype "bidirectional"))
    )
    (net (code "47") (name "Net-(PSOC4200L-P2.2)") (class "Default")
      (node (ref "3_ENCD3V3") (pin "4") (pinfunction "4_4") (pintype "bidirectional"))
      (node (ref "PSOC4200L") (pin "4") (pinfunction "P2.2_4") (pintype "bidirectional"))
      (node (ref "SHIFT3") (pin "3") (pinfunction "A1_3") (pintype "bidirectional"))
    )
    (net (code "48") (name "Net-(PSOC4200L-P2.3)") (class "Default")
      (node (ref "LIMITA3") (pin "2") (pinfunction "2_2") (pintype "bidirectional"))
      (node (ref "PSOC4200L") (pin "5") (pinfunction "P2.3_5") (pintype "bidirectional"))
    )
    (net (code "49") (name "Net-(PSOC4200L-P2.4)") (class "Default")
      (node (ref "LIMITB3") (pin "2") (pinfunction "2_2") (pintype "bidirectional"))
      (node (ref "PSOC4200L") (pin "6") (pinfunction "P2.4_6") (pintype "bidirectional"))
    )
    (net (code "50") (name "Net-(PSOC4200L-P2.5)") (class "Default")
      (node (ref "PSOC4200L") (pin "7") (pinfunction "P2.5_7") (pintype "bidirectional"))
      (node (ref "PWM3") (pin "2") (pinfunction "2_2") (pintype "bidirectional"))
    )
    (net (code "51") (name "Net-(PSOC4200L-P2.6)") (class "Default")
      (node (ref "POT3") (pin "2") (pinfunction "2_2") (pintype "bidirectional"))
      (node (ref "PSOC4200L") (pin "8") (pinfunction "P2.6_8") (pintype "bidirectional"))
    )
    (net (code "52") (name "Net-(PSOC4200L-P2.7)") (class "Default")
      (node (ref "4_ENCD3V3") (pin "2") (pinfunction "2_2") (pintype "bidirectional"))
      (node (ref "PSOC4200L") (pin "9") (pinfunction "P2.7_9") (pintype "bidirectional"))
      (node (ref "SHIFT4") (pin "5") (pinfunction "A3_5") (pintype "bidirectional"))
    )
    (net (code "53") (name "Net-(PSOC4200L-P3.0)") (class "Default")
      (node (ref "4_ENCD3V3") (pin "3") (pinfunction "3_3") (pintype "bidirectional"))
      (node (ref "PSOC4200L") (pin "18") (pinfunction "P3.0_18") (pintype "bidirectional"))
      (node (ref "SHIFT4") (pin "4") (pinfunction "A2_4") (pintype "bidirectional"))
    )
    (net (code "54") (name "Net-(PSOC4200L-P3.1)") (class "Default")
      (node (ref "4_ENCD3V3") (pin "4") (pinfunction "4_4") (pintype "bidirectional"))
      (node (ref "PSOC4200L") (pin "19") (pinfunction "P3.1_19") (pintype "bidirectional"))
      (node (ref "SHIFT4") (pin "3") (pinfunction "A1_3") (pintype "bidirectional"))
    )
    (net (code "55") (name "Net-(PSOC4200L-P3.4)") (class "Default")
      (node (ref "LIMITA4") (pin "2") (pinfunction "2_2") (pintype "bidirectional"))
      (node (ref "PSOC4200L") (pin "22") (pinfunction "P3.4_22") (pintype "bidirectional"))
    )
    (net (code "56") (name "Net-(PSOC4200L-P3.5)") (class "Default")
      (node (ref "LIMITB4") (pin "2") (pinfunction "2_2") (pintype "bidirectional"))
      (node (ref "PSOC4200L") (pin "23") (pinfunction "P3.5_23") (pintype "bidirectional"))
    )
    (net (code "57") (name "Net-(PSOC4200L-P3.6)") (class "Default")
      (node (ref "PSOC4200L") (pin "24") (pinfunction "P3.6_24") (pintype "bidirectional"))
      (node (ref "PWM4") (pin "2") (pinfunction "2_2") (pintype "bidirectional"))
    )
    (net (code "58") (name "Net-(PSOC4200L-P3.7)") (class "Default")
      (node (ref "POT4") (pin "2") (pinfunction "2_2") (pintype "bidirectional"))
      (node (ref "PSOC4200L") (pin "25") (pinfunction "P3.7_25") (pintype "bidirectional"))
    )
    (net (code "59") (name "Net-(PSOC4200L-P4.1)") (class "Default")
      (node (ref "BASIC_HEADER1") (pin "1") (pinfunction "1_1") (pintype "bidirectional"))
      (node (ref "PSOC4200L") (pin "28") (pinfunction "P4.1_28") (pintype "bidirectional"))
    )
    (net (code "60") (name "Net-(PSOC4200L-P4.2)") (class "Default")
      (node (ref "BASIC_HEADER1") (pin "2") (pinfunction "2_2") (pintype "bidirectional"))
      (node (ref "PSOC4200L") (pin "29") (pinfunction "P4.2_29") (pintype "bidirectional"))
    )
    (net (code "61") (name "Net-(PSOC4200L-P4.3)") (class "Default")
      (node (ref "BASIC_HEADER1") (pin "3") (pinfunction "3_3") (pintype "bidirectional"))
      (node (ref "PSOC4200L") (pin "30") (pinfunction "P4.3_30") (pintype "bidirectional"))
    )
    (net (code "62") (name "Net-(PSOC4200L-P4.4)") (class "Default")
      (node (ref "BASIC_HEADER1") (pin "4") (pinfunction "4_4") (pintype "bidirectional"))
      (node (ref "PSOC4200L") (pin "31") (pinfunction "P4.4_31") (pintype "bidirectional"))
    )
    (net (code "63") (name "Net-(PSOC4200L-P4.5)") (class "Default")
      (node (ref "BASIC_HEADER1") (pin "5") (pinfunction "5_5") (pintype "bidirectional"))
      (node (ref "PSOC4200L") (pin "32") (pinfunction "P4.5_32") (pintype "bidirectional"))
    )
    (net (code "64") (name "Net-(PSOC4200L-P4.6)") (class "Default")
      (node (ref "BASIC_HEADER1") (pin "6") (pinfunction "6_6") (pintype "bidirectional"))
      (node (ref "PSOC4200L") (pin "33") (pinfunction "P4.6_33") (pintype "bidirectional"))
    )
    (net (code "65") (name "Net-(PSOC4200L-P5.5)") (class "Default")
      (node (ref "BASIC_HEADER2") (pin "1") (pinfunction "1_1") (pintype "bidirectional"))
      (node (ref "PSOC4200L") (pin "55") (pinfunction "P5.5_55") (pintype "bidirectional"))
    )
    (net (code "66") (name "Net-(PSOC4200L-P6.0)") (class "Default")
      (node (ref "BASIC_HEADER2") (pin "2") (pinfunction "2_2") (pintype "bidirectional"))
      (node (ref "PSOC4200L") (pin "12") (pinfunction "P6.0_12") (pintype "bidirectional"))
    )
    (net (code "67") (name "Net-(PSOC4200L-P6.1)") (class "Default")
      (node (ref "PSOC4200L") (pin "13") (pinfunction "P6.1_13") (pintype "bidirectional"))
      (node (ref "TCAN") (pin "4") (pinfunction "RXD_4") (pintype "input"))
    )
    (net (code "68") (name "Net-(PSOC4200L-P6.2)") (class "Default")
      (node (ref "PSOC4200L") (pin "14") (pinfunction "P6.2_14") (pintype "bidirectional"))
      (node (ref "TCAN") (pin "1") (pinfunction "TXD_1") (pintype "output"))
    )
    (net (code "69") (name "Net-(PSOC4200L-P6.4{slash}P12.0)") (class "Default")
      (node (ref "BASIC_HEADER2") (pin "3") (pinfunction "3_3") (pintype "bidirectional"))
      (node (ref "PSOC4200L") (pin "15") (pinfunction "P6.4/P12.0_15") (pintype "bidirectional"))
    )
    (net (code "70") (name "Net-(PSOC4200L-P6.5{slash}P12.1)") (class "Default")
      (node (ref "BASIC_HEADER2") (pin "4") (pinfunction "4_4") (pintype "bidirectional"))
      (node (ref "PSOC4200L") (pin "16") (pinfunction "P6.5/P12.1_16") (pintype "bidirectional"))
    )
    (net (code "71") (name "Net-(PSOC4200L-P7.0)") (class "Default")
      (node (ref "BASIC_HEADER2") (pin "5") (pinfunction "5_5") (pintype "bidirectional"))
      (node (ref "PSOC4200L") (pin "37") (pinfunction "P7.0_37") (pintype "bidirectional"))
    )
    (net (code "72") (name "Net-(PSOC4200L-P7.1)") (class "Default")
      (node (ref "BASIC_HEADER2") (pin "6") (pinfunction "6_6") (pintype "bidirectional"))
      (node (ref "PSOC4200L") (pin "38") (pinfunction "P7.1_38") (pintype "bidirectional"))
    )
    (net (code "73") (name "Net-(PSOC4200L-VCCD)") (class "Default")
      (node (ref "C1") (pin "1") (pinfunction "1_1") (pintype "passive"))
      (node (ref "PSOC4200L") (pin "48") (pinfunction "VCCD_48") (pintype "power_in"))
    )
    (net (code "74") (name "Net-(SHIFT1-B1)") (class "Default")
      (node (ref "1_ENCD5V") (pin "4") (pinfunction "4_4") (pintype "bidirectional"))
      (node (ref "SHIFT1") (pin "8") (pinfunction "B1_8") (pintype "bidirectional"))
    )
    (net (code "75") (name "Net-(SHIFT1-B2)") (class "Default")
      (node (ref "1_ENCD5V") (pin "3") (pinfunction "3_3") (pintype "bidirectional"))
      (node (ref "SHIFT1") (pin "7") (pinfunction "B2_7") (pintype "bidirectional"))
    )
    (net (code "76") (name "Net-(SHIFT1-B3)") (class "Default")
      (node (ref "1_ENCD5V") (pin "2") (pinfunction "2_2") (pintype "bidirectional"))
      (node (ref "SHIFT1") (pin "6") (pinfunction "B3_6") (pintype "bidirectional"))
    )
    (net (code "77") (name "Net-(SHIFT2-B1)") (class "Default")
      (node (ref "2_ENCD5V") (pin "4") (pinfunction "4_4") (pintype "bidirectional"))
      (node (ref "SHIFT2") (pin "8") (pinfunction "B1_8") (pintype "bidirectional"))
    )
    (net (code "78") (name "Net-(SHIFT2-B2)") (class "Default")
      (node (ref "2_ENCD5V") (pin "3") (pinfunction "3_3") (pintype "bidirectional"))
      (node (ref "SHIFT2") (pin "7") (pinfunction "B2_7") (pintype "bidirectional"))
    )
    (net (code "79") (name "Net-(SHIFT2-B3)") (class "Default")
      (node (ref "2_ENCD5V") (pin "2") (pinfunction "2_2") (pintype "bidirectional"))
      (node (ref "SHIFT2") (pin "6") (pinfunction "B3_6") (pintype "bidirectional"))
    )
    (net (code "80") (name "Net-(SHIFT3-B1)") (class "Default")
      (node (ref "3_ENCD5V") (pin "4") (pinfunction "4_4") (pintype "bidirectional"))
      (node (ref "SHIFT3") (pin "8") (pinfunction "B1_8") (pintype "bidirectional"))
    )
    (net (code "81") (name "Net-(SHIFT3-B2)") (class "Default")
      (node (ref "3_ENCD5V") (pin "3") (pinfunction "3_3") (pintype "bidirectional"))
      (node (ref "SHIFT3") (pin "7") (pinfunction "B2_7") (pintype "bidirectional"))
    )
    (net (code "82") (name "Net-(SHIFT3-B3)") (class "Default")
      (node (ref "3_ENCD5V") (pin "2") (pinfunction "2_2") (pintype "bidirectional"))
      (node (ref "SHIFT3") (pin "6") (pinfunction "B3_6") (pintype "bidirectional"))
    )
    (net (code "83") (name "Net-(SHIFT4-B1)") (class "Default")
      (node (ref "4_ENCD5V") (pin "4") (pinfunction "4_4") (pintype "bidirectional"))
      (node (ref "SHIFT4") (pin "8") (pinfunction "B1_8") (pintype "bidirectional"))
    )
    (net (code "84") (name "Net-(SHIFT4-B2)") (class "Default")
      (node (ref "4_ENCD5V") (pin "3") (pinfunction "3_3") (pintype "bidirectional"))
      (node (ref "SHIFT4") (pin "7") (pinfunction "B2_7") (pintype "bidirectional"))
    )
    (net (code "85") (name "Net-(SHIFT4-B3)") (class "Default")
      (node (ref "4_ENCD5V") (pin "2") (pinfunction "2_2") (pintype "bidirectional"))
      (node (ref "SHIFT4") (pin "6") (pinfunction "B3_6") (pintype "bidirectional"))
    )
  )
)
